# blink1_v1a.net
KiCad netlist of a schematic drawn in EAGLE
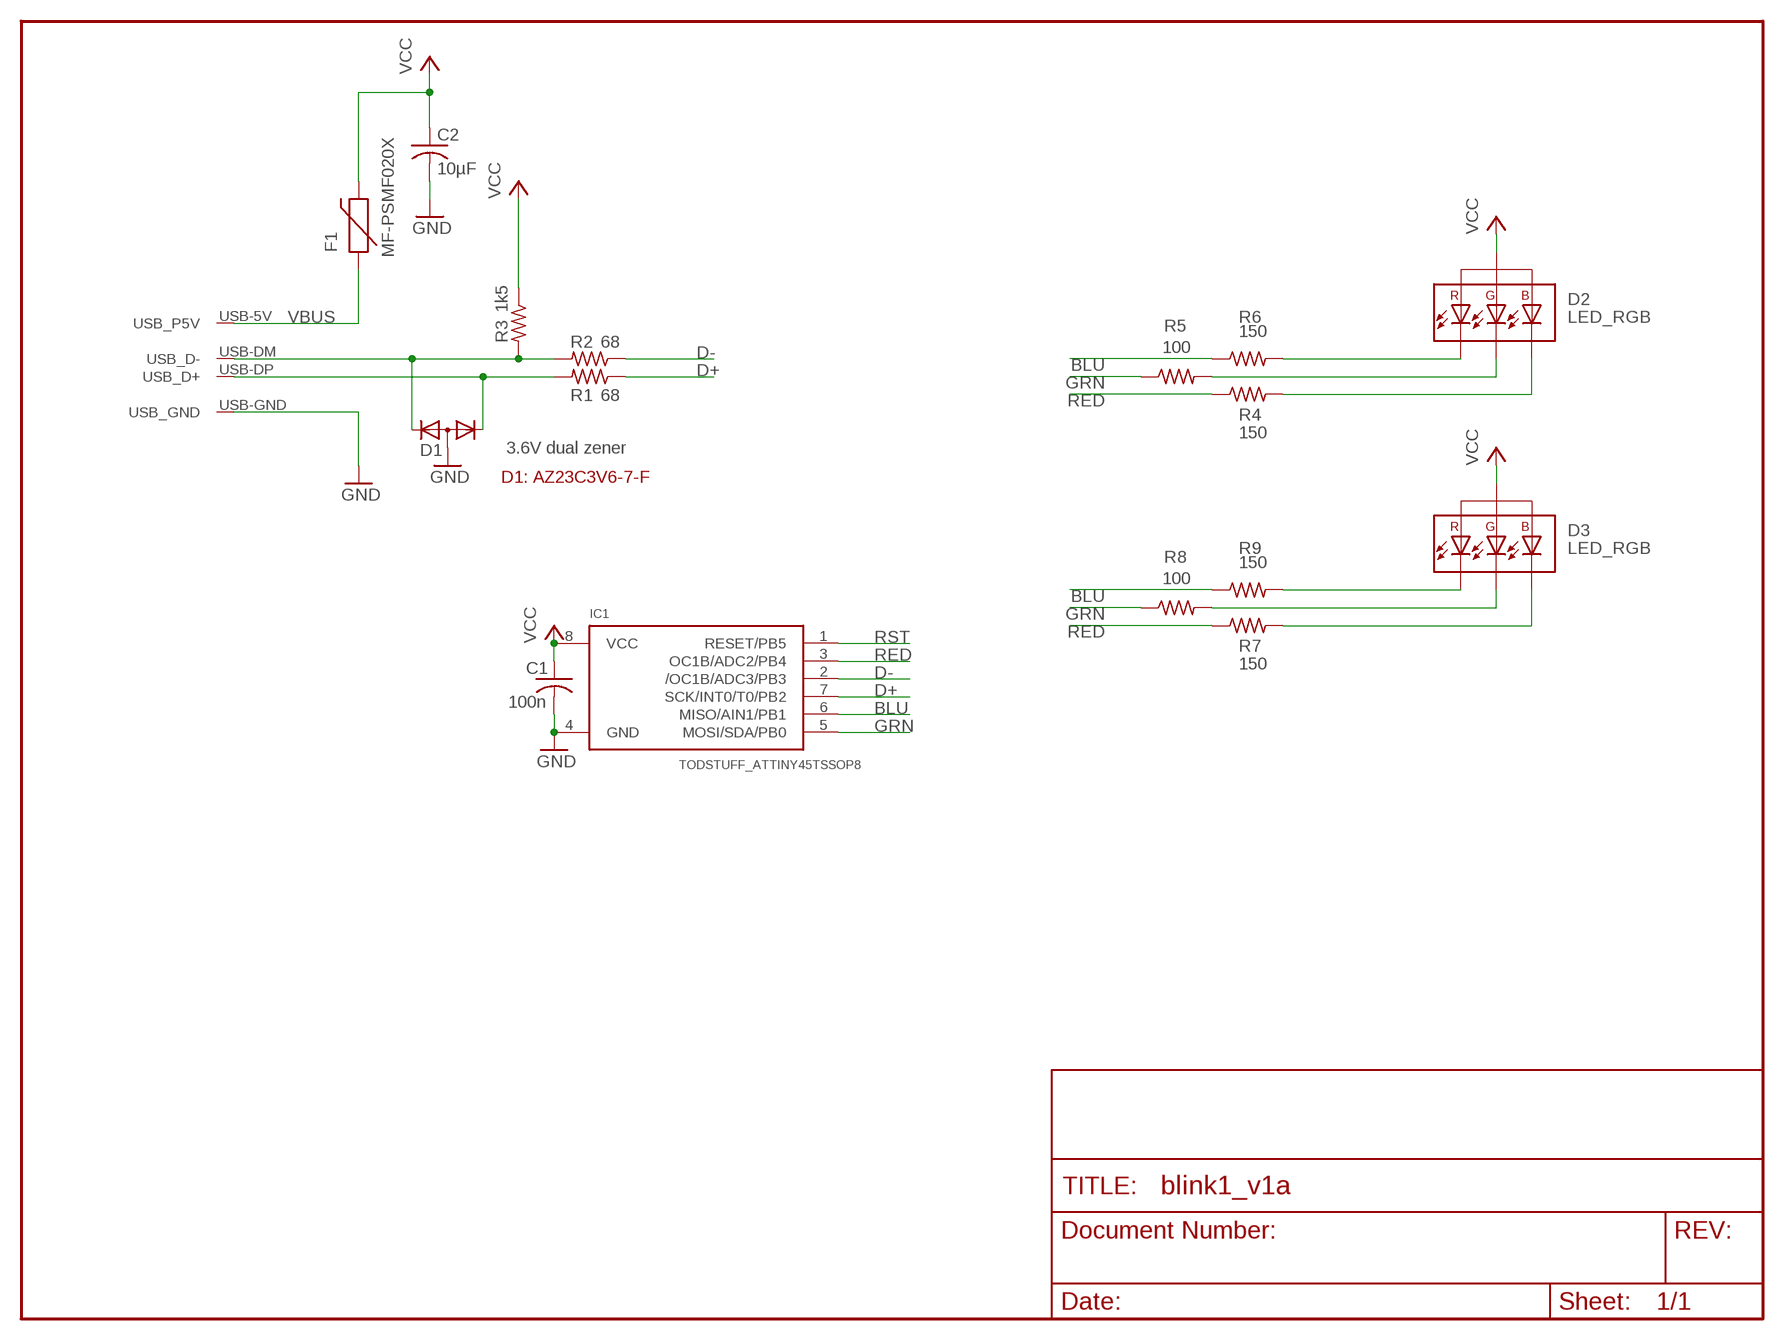
[diagram p0: schematic, sheet 1]

(export (version "E")
  (design (tool "Eeschema 10.0.6"))
  (components
    (comp (ref "C1")
      (value "100n")
      (footprint "eagle-import:C0402")
      (libsource (lib "eagle-import") (part "C-USC0402"))
    )
    (comp (ref "C2")
      (value "10µF")
      (footprint "eagle-import:C0603")
      (libsource (lib "eagle-import") (part "C-USC0603"))
    )
    (comp (ref "D1")
      (value "3.6V dual zener")
      (footprint "eagle-import:SOT23")
      (libsource (lib "eagle-import") (part "DIODE-2CA|ACSOT23"))
    )
    (comp (ref "D2")
      (value "LED_RGB")
      (footprint "eagle-import:LED_1010")
      (libsource (lib "eagle-import") (part "LED_RGB"))
    )
    (comp (ref "D3")
      (value "LED_RGB")
      (footprint "eagle-import:LED_1010")
      (libsource (lib "eagle-import") (part "LED_RGB"))
    )
    (comp (ref "F1")
      (value "MF-PSMF020X")
      (footprint "eagle-import:0805")
      (libsource (lib "eagle-import") (part "PTC0805"))
    )
    (comp (ref "IC1")
      (value "TODSTUFF_ATTINY45TSSOP8")
      (footprint "eagle-import:TSSOP8")
      (libsource (lib "eagle-import") (part "TODSTUFF_ATTINY45TSSOP8"))
    )
    (comp (ref "R1")
      (value "68")
      (footprint "eagle-import:R0402")
      (libsource (lib "eagle-import") (part "R-US_R0402"))
    )
    (comp (ref "R2")
      (value "68")
      (footprint "eagle-import:R0402")
      (libsource (lib "eagle-import") (part "R-US_R0402"))
    )
    (comp (ref "R3")
      (value "1k5")
      (footprint "eagle-import:R0402")
      (libsource (lib "eagle-import") (part "R-US_R0402"))
    )
    (comp (ref "R4")
      (value "150")
      (footprint "eagle-import:R0402")
      (libsource (lib "eagle-import") (part "R-US_R0402"))
    )
    (comp (ref "R5")
      (value "100")
      (footprint "eagle-import:R0402")
      (libsource (lib "eagle-import") (part "R-US_R0402"))
    )
    (comp (ref "R6")
      (value "150")
      (footprint "eagle-import:R0402")
      (libsource (lib "eagle-import") (part "R-US_R0402"))
    )
    (comp (ref "R7")
      (value "150")
      (footprint "eagle-import:R0402")
      (libsource (lib "eagle-import") (part "R-US_R0402"))
    )
    (comp (ref "R8")
      (value "100")
      (footprint "eagle-import:R0402")
      (libsource (lib "eagle-import") (part "R-US_R0402"))
    )
    (comp (ref "R9")
      (value "150")
      (footprint "eagle-import:R0402")
      (libsource (lib "eagle-import") (part "R-US_R0402"))
    )
    (comp (ref "U$1")
      (value "PCB-USB-DEV")
      (footprint "eagle-import:PCB-USB-PAC")
      (libsource (lib "eagle-import") (part "PCB-USB-DEV"))
    )
  )
  (nets
    (net (code "1") (name "/BLU") (class "Default")
      (node (ref "IC1") (pin "6") (pinfunction "MISO/AIN1/PB1_6") (pintype "bidirectional"))
      (node (ref "R6") (pin "1") (pinfunction "1_1") (pintype "passive"))
      (node (ref "R9") (pin "1") (pinfunction "1_1") (pintype "passive"))
    )
    (net (code "2") (name "/D+") (class "Default")
      (node (ref "IC1") (pin "7") (pinfunction "SCK/INT0/T0/PB2_7") (pintype "bidirectional"))
      (node (ref "R1") (pin "1") (pinfunction "1_1") (pintype "passive"))
    )
    (net (code "3") (name "/D-") (class "Default")
      (node (ref "IC1") (pin "2") (pinfunction "/OC1B/ADC3/PB3_2") (pintype "bidirectional"))
      (node (ref "R2") (pin "1") (pinfunction "1_1") (pintype "passive"))
    )
    (net (code "4") (name "/GRN") (class "Default")
      (node (ref "IC1") (pin "5") (pinfunction "MOSI/SDA/PB0_5") (pintype "bidirectional"))
      (node (ref "R5") (pin "1") (pinfunction "1_1") (pintype "passive"))
      (node (ref "R8") (pin "1") (pinfunction "1_1") (pintype "passive"))
    )
    (net (code "5") (name "/RED") (class "Default")
      (node (ref "IC1") (pin "3") (pinfunction "OC1B/ADC2/PB4_3") (pintype "bidirectional"))
      (node (ref "R4") (pin "1") (pinfunction "1_1") (pintype "passive"))
      (node (ref "R7") (pin "1") (pinfunction "1_1") (pintype "passive"))
    )
    (net (code "6") (name "/RST") (class "Default")
      (node (ref "IC1") (pin "1") (pinfunction "RESET/PB5_1") (pintype "bidirectional"))
    )
    (net (code "7") (name "/VBUS") (class "Default")
      (node (ref "F1") (pin "1") (pinfunction "1_1") (pintype "bidirectional"))
      (node (ref "U$1") (pin "USB-5V") (pinfunction "USB_P5V_USB-5V") (pintype "bidirectional"))
    )
    (net (code "8") (name "GND") (class "Default")
      (node (ref "C1") (pin "2") (pinfunction "2_2") (pintype "passive"))
      (node (ref "C2") (pin "2") (pinfunction "2_2") (pintype "passive"))
      (node (ref "D1") (pin "3") (pinfunction "A_3") (pintype "passive"))
      (node (ref "IC1") (pin "4") (pinfunction "GND_4") (pintype "bidirectional"))
      (node (ref "U$1") (pin "USB-GND") (pinfunction "USB_GND_USB-GND") (pintype "bidirectional"))
    )
    (net (code "9") (name "Net-(D1-K1)") (class "Default")
      (node (ref "D1") (pin "1") (pinfunction "K1_1") (pintype "passive"))
      (node (ref "R1") (pin "2") (pinfunction "2_2") (pintype "passive"))
      (node (ref "U$1") (pin "USB-DP") (pinfunction "USB_D+_USB-DP") (pintype "bidirectional"))
    )
    (net (code "10") (name "Net-(D1-K2)") (class "Default")
      (node (ref "D1") (pin "2") (pinfunction "K2_2") (pintype "passive"))
      (node (ref "R2") (pin "2") (pinfunction "2_2") (pintype "passive"))
      (node (ref "R3") (pin "2") (pinfunction "2_2") (pintype "passive"))
      (node (ref "U$1") (pin "USB-DM") (pinfunction "USB_D-_USB-DM") (pintype "bidirectional"))
    )
    (net (code "11") (name "Net-(D2-C_B)") (class "Default")
      (node (ref "D2") (pin "3") (pinfunction "C_B_3") (pintype "passive"))
      (node (ref "R4") (pin "2") (pinfunction "2_2") (pintype "passive"))
    )
    (net (code "12") (name "Net-(D2-C_G)") (class "Default")
      (node (ref "D2") (pin "4") (pinfunction "C_G_4") (pintype "passive"))
      (node (ref "R5") (pin "2") (pinfunction "2_2") (pintype "passive"))
    )
    (net (code "13") (name "Net-(D2-C_R)") (class "Default")
      (node (ref "D2") (pin "2") (pinfunction "C_R_2") (pintype "passive"))
      (node (ref "R6") (pin "2") (pinfunction "2_2") (pintype "passive"))
    )
    (net (code "14") (name "Net-(D3-C_B)") (class "Default")
      (node (ref "D3") (pin "3") (pinfunction "C_B_3") (pintype "passive"))
      (node (ref "R7") (pin "2") (pinfunction "2_2") (pintype "passive"))
    )
    (net (code "15") (name "Net-(D3-C_G)") (class "Default")
      (node (ref "D3") (pin "4") (pinfunction "C_G_4") (pintype "passive"))
      (node (ref "R8") (pin "2") (pinfunction "2_2") (pintype "passive"))
    )
    (net (code "16") (name "Net-(D3-C_R)") (class "Default")
      (node (ref "D3") (pin "2") (pinfunction "C_R_2") (pintype "passive"))
      (node (ref "R9") (pin "2") (pinfunction "2_2") (pintype "passive"))
    )
    (net (code "17") (name "VCC") (class "Default")
      (node (ref "C1") (pin "1") (pinfunction "1_1") (pintype "passive"))
      (node (ref "C2") (pin "1") (pinfunction "1_1") (pintype "passive"))
      (node (ref "D2") (pin "1") (pinfunction "A_1") (pintype "passive"))
      (node (ref "D3") (pin "1") (pinfunction "A_1") (pintype "passive"))
      (node (ref "F1") (pin "2") (pinfunction "2_2") (pintype "bidirectional"))
      (node (ref "IC1") (pin "8") (pinfunction "VCC_8") (pintype "bidirectional"))
      (node (ref "R3") (pin "1") (pinfunction "1_1") (pintype "passive"))
    )
  )
)
